# PCB_Reflow0xPIT.net
KiCad netlist of a schematic drawn in EAGLE
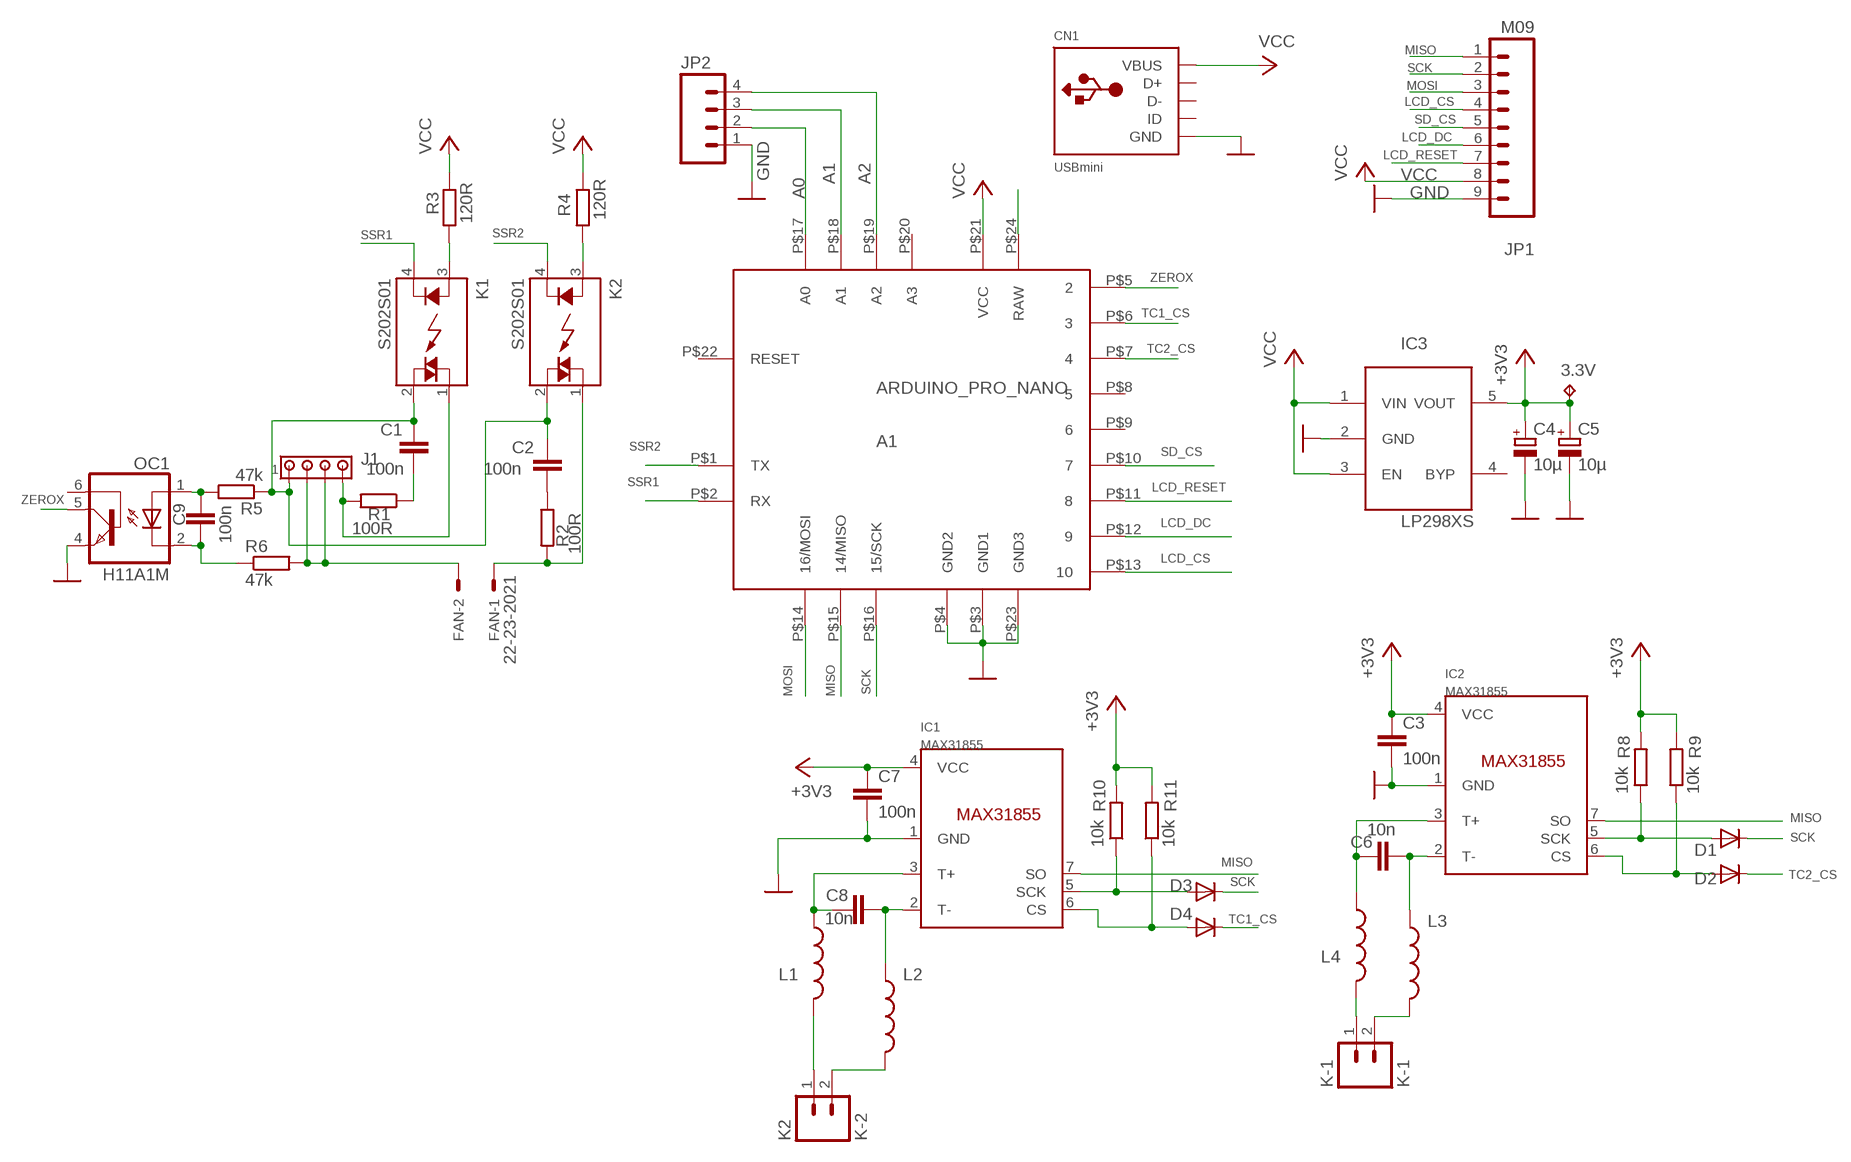
[diagram p0: schematic, sheet 1]

(export (version "E")
  (design (tool "Eeschema 10.0.6"))
  (components
    (comp (ref "3.3V")
      (value "TPTP08R")
      (footprint "eagle-import:TP08R")
      (libsource (lib "eagle-import") (part "TPTP08R"))
    )
    (comp (ref "A1")
      (value "ARDUINO_PRO_NANO")
      (footprint "eagle-import:ARDUINO_PRO_NANO")
      (libsource (lib "eagle-import") (part "ARDUINO_PRO_NANO"))
    )
    (comp (ref "C1")
      (value "100n")
      (footprint "eagle-import:C102-043X133")
      (libsource (lib "eagle-import") (part "C-EU102-043X133"))
    )
    (comp (ref "C2")
      (value "100n")
      (footprint "eagle-import:C102-043X133")
      (libsource (lib "eagle-import") (part "C-EU102-043X133"))
    )
    (comp (ref "C3")
      (value "100n")
      (footprint "eagle-import:C0805")
      (libsource (lib "eagle-import") (part "C-EUC0805"))
    )
    (comp (ref "C4")
      (value "10µ")
      (footprint "eagle-import:C_6032-28R")
      (libsource (lib "eagle-import") (part "CPOL-EUC/6032-28R"))
    )
    (comp (ref "C5")
      (value "10µ")
      (footprint "eagle-import:C_6032-28R")
      (libsource (lib "eagle-import") (part "CPOL-EUC/6032-28R"))
    )
    (comp (ref "C6")
      (value "10n")
      (footprint "eagle-import:C0603")
      (libsource (lib "eagle-import") (part "C-EUC0603"))
    )
    (comp (ref "C7")
      (value "100n")
      (footprint "eagle-import:C0805")
      (libsource (lib "eagle-import") (part "C-EUC0805"))
    )
    (comp (ref "C8")
      (value "10n")
      (footprint "eagle-import:C0603")
      (libsource (lib "eagle-import") (part "C-EUC0603"))
    )
    (comp (ref "C9")
      (value "100n")
      (footprint "eagle-import:C025-025X050")
      (libsource (lib "eagle-import") (part "C-EU025-025X050"))
    )
    (comp (ref "CN1")
      (value "USBmini")
      (footprint "eagle-import:USB-MINIB")
      (libsource (lib "eagle-import") (part "USBMINIB"))
    )
    (comp (ref "D1")
      (value "1N4148")
      (footprint "eagle-import:SOD-123")
      (libsource (lib "eagle-import") (part "DIODESOD-123"))
    )
    (comp (ref "D2")
      (value "1N4148")
      (footprint "eagle-import:SOD-123")
      (libsource (lib "eagle-import") (part "DIODESOD-123"))
    )
    (comp (ref "D3")
      (value "1N4148")
      (footprint "eagle-import:SOD-123")
      (libsource (lib "eagle-import") (part "DIODESOD-123"))
    )
    (comp (ref "D4")
      (value "1N4148")
      (footprint "eagle-import:SOD-123")
      (libsource (lib "eagle-import") (part "DIODESOD-123"))
    )
    (comp (ref "FAN")
      (value "22-23-2021")
      (footprint "eagle-import:22-23-2021")
      (fields (field (name "MF") "MOLEX"))
      (libsource (lib "eagle-import") (part "22-23-2021"))
    )
    (comp (ref "IC1")
      (value "MAX31855")
      (footprint "eagle-import:SOIC8")
      (libsource (lib "eagle-import") (part "MAX31855"))
    )
    (comp (ref "IC2")
      (value "MAX31855")
      (footprint "eagle-import:SOIC8")
      (libsource (lib "eagle-import") (part "MAX31855"))
    )
    (comp (ref "IC3")
      (value "LP298XS")
      (footprint "eagle-import:SOT23-5L")
      (libsource (lib "eagle-import") (part "LP298XS"))
    )
    (comp (ref "J1")
      (value "MTA04-156")
      (footprint "eagle-import:1X4MTA")
      (libsource (lib "eagle-import") (part "MTA04-156"))
    )
    (comp (ref "JP1")
      (value "M09")
      (footprint "eagle-import:1X09")
      (libsource (lib "eagle-import") (part "M09"))
    )
    (comp (ref "JP2")
      (value "M04LOCK")
      (footprint "eagle-import:1X04_LOCK")
      (libsource (lib "eagle-import") (part "M04LOCK"))
    )
    (comp (ref "K-1")
      (value "K-1")
      (footprint "eagle-import:JST-2-PTH")
      (libsource (lib "eagle-import") (part "M02JST-PTH-2"))
    )
    (comp (ref "K-2")
      (value "K2")
      (footprint "eagle-import:JST-2-PTH")
      (libsource (lib "eagle-import") (part "M02JST-PTH-2"))
    )
    (comp (ref "K1")
      (value "S202S01")
      (footprint "eagle-import:S102S01")
      (fields (field (name "MPN") "S202S01F"))
      (libsource (lib "eagle-import") (part "S?202S01"))
    )
    (comp (ref "K2")
      (value "S202S01")
      (footprint "eagle-import:S102S01")
      (fields (field (name "MPN") "S202S01F"))
      (libsource (lib "eagle-import") (part "S?202S01"))
    )
    (comp (ref "L1")
      (value "INDUCTOR0402")
      (footprint "eagle-import:C0402")
      (libsource (lib "eagle-import") (part "INDUCTOR0402"))
    )
    (comp (ref "L2")
      (value "INDUCTOR0402")
      (footprint "eagle-import:C0402")
      (libsource (lib "eagle-import") (part "INDUCTOR0402"))
    )
    (comp (ref "L3")
      (value "INDUCTOR0402")
      (footprint "eagle-import:C0402")
      (libsource (lib "eagle-import") (part "INDUCTOR0402"))
    )
    (comp (ref "L4")
      (value "INDUCTOR0402")
      (footprint "eagle-import:C0402")
      (libsource (lib "eagle-import") (part "INDUCTOR0402"))
    )
    (comp (ref "OC1")
      (value "H11A1M")
      (footprint "eagle-import:DIL06")
      (fields (field (name "MPN") "H11A1-M"))
      (libsource (lib "eagle-import") (part "H11A?M1"))
    )
    (comp (ref "R1")
      (value "100R")
      (footprint "eagle-import:0207_5V")
      (libsource (lib "eagle-import") (part "R-EU_0207/5V"))
    )
    (comp (ref "R2")
      (value "100R")
      (footprint "eagle-import:0207_5V")
      (libsource (lib "eagle-import") (part "R-EU_0207/5V"))
    )
    (comp (ref "R3")
      (value "120R")
      (footprint "eagle-import:M0805")
      (libsource (lib "eagle-import") (part "R-EU_M0805"))
    )
    (comp (ref "R4")
      (value "120R")
      (footprint "eagle-import:M0805")
      (libsource (lib "eagle-import") (part "R-EU_M0805"))
    )
    (comp (ref "R5")
      (value "47k")
      (footprint "eagle-import:0207_2V")
      (libsource (lib "eagle-import") (part "R-EU_0207/2V"))
    )
    (comp (ref "R6")
      (value "47k")
      (footprint "eagle-import:0207_2V")
      (libsource (lib "eagle-import") (part "R-EU_0207/2V"))
    )
    (comp (ref "R8")
      (value "10k")
      (footprint "eagle-import:M1206")
      (libsource (lib "eagle-import") (part "R-EU_M1206"))
    )
    (comp (ref "R9")
      (value "10k")
      (footprint "eagle-import:M1206")
      (libsource (lib "eagle-import") (part "R-EU_M1206"))
    )
    (comp (ref "R10")
      (value "10k")
      (footprint "eagle-import:M1206")
      (libsource (lib "eagle-import") (part "R-EU_M1206"))
    )
    (comp (ref "R11")
      (value "10k")
      (footprint "eagle-import:M1206")
      (libsource (lib "eagle-import") (part "R-EU_M1206"))
    )
  )
  (nets
    (net (code "1") (name "+3V3") (class "Default")
      (node (ref "3.3V") (pin "TP") (pinfunction "TP_TP") (pintype "input"))
      (node (ref "C3") (pin "1") (pinfunction "1_1") (pintype "passive"))
      (node (ref "C4") (pin "+") (pinfunction "+_+") (pintype "passive"))
      (node (ref "C5") (pin "+") (pinfunction "+_+") (pintype "passive"))
      (node (ref "C7") (pin "1") (pinfunction "1_1") (pintype "passive"))
      (node (ref "IC1") (pin "4") (pinfunction "VCC_4") (pintype "power_in"))
      (node (ref "IC2") (pin "4") (pinfunction "VCC_4") (pintype "power_in"))
      (node (ref "IC3") (pin "5") (pinfunction "VOUT_5") (pintype "bidirectional"))
      (node (ref "R10") (pin "2") (pinfunction "2_2") (pintype "passive"))
      (node (ref "R11") (pin "2") (pinfunction "2_2") (pintype "passive"))
      (node (ref "R8") (pin "2") (pinfunction "2_2") (pintype "passive"))
      (node (ref "R9") (pin "2") (pinfunction "2_2") (pintype "passive"))
    )
    (net (code "2") (name "/A0") (class "Default")
      (node (ref "A1") (pin "P$17") (pinfunction "A0_P$17") (pintype "bidirectional"))
      (node (ref "JP2") (pin "2") (pinfunction "2_2") (pintype "passive"))
    )
    (net (code "3") (name "/A1") (class "Default")
      (node (ref "A1") (pin "P$18") (pinfunction "A1_P$18") (pintype "bidirectional"))
      (node (ref "JP2") (pin "3") (pinfunction "3_3") (pintype "passive"))
    )
    (net (code "4") (name "/A2") (class "Default")
      (node (ref "A1") (pin "P$19") (pinfunction "A2_P$19") (pintype "bidirectional"))
      (node (ref "JP2") (pin "4") (pinfunction "4_4") (pintype "passive"))
    )
    (net (code "5") (name "/LCD_CS") (class "Default")
      (node (ref "A1") (pin "P$13") (pinfunction "10_P$13") (pintype "bidirectional"))
      (node (ref "JP1") (pin "4") (pinfunction "4_4") (pintype "passive"))
    )
    (net (code "6") (name "/LCD_DC") (class "Default")
      (node (ref "A1") (pin "P$12") (pinfunction "9_P$12") (pintype "bidirectional"))
      (node (ref "JP1") (pin "6") (pinfunction "6_6") (pintype "passive"))
    )
    (net (code "7") (name "/LCD_RESET") (class "Default")
      (node (ref "A1") (pin "P$11") (pinfunction "8_P$11") (pintype "bidirectional"))
      (node (ref "JP1") (pin "7") (pinfunction "7_7") (pintype "passive"))
    )
    (net (code "8") (name "/MISO") (class "Default")
      (node (ref "A1") (pin "P$15") (pinfunction "14/MISO_P$15") (pintype "bidirectional"))
      (node (ref "IC1") (pin "7") (pinfunction "SO_7") (pintype "output"))
      (node (ref "IC2") (pin "7") (pinfunction "SO_7") (pintype "output"))
      (node (ref "JP1") (pin "1") (pinfunction "1_1") (pintype "passive"))
    )
    (net (code "9") (name "/MOSI") (class "Default")
      (node (ref "A1") (pin "P$14") (pinfunction "16/MOSI_P$14") (pintype "bidirectional"))
      (node (ref "JP1") (pin "3") (pinfunction "3_3") (pintype "passive"))
    )
    (net (code "10") (name "/SCK") (class "Default")
      (node (ref "A1") (pin "P$16") (pinfunction "15/SCK_P$16") (pintype "bidirectional"))
      (node (ref "D1") (pin "C") (pinfunction "C_C") (pintype "passive"))
      (node (ref "D3") (pin "C") (pinfunction "C_C") (pintype "passive"))
      (node (ref "JP1") (pin "2") (pinfunction "2_2") (pintype "passive"))
    )
    (net (code "11") (name "/SD_CS") (class "Default")
      (node (ref "A1") (pin "P$10") (pinfunction "7_P$10") (pintype "bidirectional"))
      (node (ref "JP1") (pin "5") (pinfunction "5_5") (pintype "passive"))
    )
    (net (code "12") (name "/SSR1") (class "Default")
      (node (ref "A1") (pin "P$2") (pinfunction "RX_P$2") (pintype "bidirectional"))
      (node (ref "K1") (pin "4") (pinfunction "K_4") (pintype "passive"))
    )
    (net (code "13") (name "/SSR2") (class "Default")
      (node (ref "A1") (pin "P$1") (pinfunction "TX_P$1") (pintype "bidirectional"))
      (node (ref "K2") (pin "4") (pinfunction "K_4") (pintype "passive"))
    )
    (net (code "14") (name "/TC1_CS") (class "Default")
      (node (ref "A1") (pin "P$6") (pinfunction "3_P$6") (pintype "bidirectional"))
      (node (ref "D4") (pin "C") (pinfunction "C_C") (pintype "passive"))
    )
    (net (code "15") (name "/TC2_CS") (class "Default")
      (node (ref "A1") (pin "P$7") (pinfunction "4_P$7") (pintype "bidirectional"))
      (node (ref "D2") (pin "C") (pinfunction "C_C") (pintype "passive"))
    )
    (net (code "16") (name "/ZEROX") (class "Default")
      (node (ref "A1") (pin "P$5") (pinfunction "2_P$5") (pintype "bidirectional"))
      (node (ref "OC1") (pin "5") (pinfunction "COL_5") (pintype "passive"))
    )
    (net (code "17") (name "GND") (class "Default")
      (node (ref "A1") (pin "P$23") (pinfunction "GND3_P$23") (pintype "power_in"))
      (node (ref "A1") (pin "P$3") (pinfunction "GND1_P$3") (pintype "power_in"))
      (node (ref "A1") (pin "P$4") (pinfunction "GND2_P$4") (pintype "power_in"))
      (node (ref "C3") (pin "2") (pinfunction "2_2") (pintype "passive"))
      (node (ref "C4") (pin "-") (pinfunction "-_-") (pintype "passive"))
      (node (ref "C5") (pin "-") (pinfunction "-_-") (pintype "passive"))
      (node (ref "C7") (pin "2") (pinfunction "2_2") (pintype "passive"))
      (node (ref "CN1") (pin "GND") (pinfunction "GND_GND") (pintype "power_in"))
      (node (ref "IC1") (pin "1") (pinfunction "GND_1") (pintype "power_in"))
      (node (ref "IC2") (pin "1") (pinfunction "GND_1") (pintype "power_in"))
      (node (ref "IC3") (pin "2") (pinfunction "GND_2") (pintype "bidirectional"))
      (node (ref "JP1") (pin "9") (pinfunction "9_9") (pintype "passive"))
      (node (ref "JP2") (pin "1") (pinfunction "1_1") (pintype "passive"))
      (node (ref "OC1") (pin "4") (pinfunction "EMI_4") (pintype "passive"))
    )
    (net (code "18") (name "Net-(C1-Pad2)") (class "Default")
      (node (ref "C1") (pin "2") (pinfunction "2_2") (pintype "passive"))
      (node (ref "R1") (pin "1") (pinfunction "1_1") (pintype "passive"))
    )
    (net (code "19") (name "Net-(C2-Pad2)") (class "Default")
      (node (ref "C2") (pin "2") (pinfunction "2_2") (pintype "passive"))
      (node (ref "R2") (pin "1") (pinfunction "1_1") (pintype "passive"))
    )
    (net (code "20") (name "Net-(FANA-S)") (class "Default")
      (node (ref "FAN") (pin "1") (pinfunction "S_1") (pintype "passive"))
      (node (ref "K2") (pin "1") (pinfunction "DS1_1") (pintype "passive"))
      (node (ref "R2") (pin "2") (pinfunction "2_2") (pintype "passive"))
    )
    (net (code "21") (name "Net-(FANB-S)") (class "Default")
      (node (ref "FAN") (pin "2") (pinfunction "S_2") (pintype "passive"))
      (node (ref "J1") (pin "2") (pinfunction "2_2") (pintype "passive"))
      (node (ref "J1") (pin "3") (pinfunction "3_3") (pintype "passive"))
      (node (ref "R6") (pin "2") (pinfunction "2_2") (pintype "passive"))
    )
    (net (code "22") (name "Net-(IC1-CS)") (class "Default")
      (node (ref "D4") (pin "A") (pinfunction "A_A") (pintype "passive"))
      (node (ref "IC1") (pin "6") (pinfunction "CS_6") (pintype "input"))
      (node (ref "R11") (pin "1") (pinfunction "1_1") (pintype "passive"))
    )
    (net (code "23") (name "Net-(IC1-SCK)") (class "Default")
      (node (ref "D3") (pin "A") (pinfunction "A_A") (pintype "passive"))
      (node (ref "IC1") (pin "5") (pinfunction "SCK_5") (pintype "input"))
      (node (ref "R10") (pin "1") (pinfunction "1_1") (pintype "passive"))
    )
    (net (code "24") (name "Net-(IC1-T+)") (class "Default")
      (node (ref "C8") (pin "1") (pinfunction "1_1") (pintype "passive"))
      (node (ref "IC1") (pin "3") (pinfunction "T+_3") (pintype "input"))
      (node (ref "L1") (pin "1") (pinfunction "1_1") (pintype "passive"))
    )
    (net (code "25") (name "Net-(IC1-T-)") (class "Default")
      (node (ref "C8") (pin "2") (pinfunction "2_2") (pintype "passive"))
      (node (ref "IC1") (pin "2") (pinfunction "T-_2") (pintype "input"))
      (node (ref "L2") (pin "1") (pinfunction "1_1") (pintype "passive"))
    )
    (net (code "26") (name "Net-(IC2-CS)") (class "Default")
      (node (ref "D2") (pin "A") (pinfunction "A_A") (pintype "passive"))
      (node (ref "IC2") (pin "6") (pinfunction "CS_6") (pintype "input"))
      (node (ref "R9") (pin "1") (pinfunction "1_1") (pintype "passive"))
    )
    (net (code "27") (name "Net-(IC2-SCK)") (class "Default")
      (node (ref "D1") (pin "A") (pinfunction "A_A") (pintype "passive"))
      (node (ref "IC2") (pin "5") (pinfunction "SCK_5") (pintype "input"))
      (node (ref "R8") (pin "1") (pinfunction "1_1") (pintype "passive"))
    )
    (net (code "28") (name "Net-(IC2-T+)") (class "Default")
      (node (ref "C6") (pin "1") (pinfunction "1_1") (pintype "passive"))
      (node (ref "IC2") (pin "3") (pinfunction "T+_3") (pintype "input"))
      (node (ref "L4") (pin "1") (pinfunction "1_1") (pintype "passive"))
    )
    (net (code "29") (name "Net-(IC2-T-)") (class "Default")
      (node (ref "C6") (pin "2") (pinfunction "2_2") (pintype "passive"))
      (node (ref "IC2") (pin "2") (pinfunction "T-_2") (pintype "input"))
      (node (ref "L3") (pin "1") (pinfunction "1_1") (pintype "passive"))
    )
    (net (code "30") (name "Net-(K-1-Pad1)") (class "Default")
      (node (ref "K-1") (pin "1") (pinfunction "1_1") (pintype "passive"))
      (node (ref "L4") (pin "2") (pinfunction "2_2") (pintype "passive"))
    )
    (net (code "31") (name "Net-(K-1-Pad2)") (class "Default")
      (node (ref "K-1") (pin "2") (pinfunction "2_2") (pintype "passive"))
      (node (ref "L3") (pin "2") (pinfunction "2_2") (pintype "passive"))
    )
    (net (code "32") (name "Net-(K-2-Pad1)") (class "Default")
      (node (ref "K-2") (pin "1") (pinfunction "1_1") (pintype "passive"))
      (node (ref "L1") (pin "2") (pinfunction "2_2") (pintype "passive"))
    )
    (net (code "33") (name "Net-(K-2-Pad2)") (class "Default")
      (node (ref "K-2") (pin "2") (pinfunction "2_2") (pintype "passive"))
      (node (ref "L2") (pin "2") (pinfunction "2_2") (pintype "passive"))
    )
    (net (code "34") (name "Net-(K1-A)") (class "Default")
      (node (ref "K1") (pin "3") (pinfunction "A_3") (pintype "passive"))
      (node (ref "R3") (pin "2") (pinfunction "2_2") (pintype "passive"))
    )
    (net (code "35") (name "Net-(K1-DS1)") (class "Default")
      (node (ref "J1") (pin "4") (pinfunction "4_4") (pintype "passive"))
      (node (ref "K1") (pin "1") (pinfunction "DS1_1") (pintype "passive"))
      (node (ref "R1") (pin "2") (pinfunction "2_2") (pintype "passive"))
    )
    (net (code "36") (name "Net-(K1-DS2)") (class "Default")
      (node (ref "C1") (pin "1") (pinfunction "1_1") (pintype "passive"))
      (node (ref "C2") (pin "1") (pinfunction "1_1") (pintype "passive"))
      (node (ref "J1") (pin "1") (pinfunction "1_1") (pintype "passive"))
      (node (ref "K1") (pin "2") (pinfunction "DS2_2") (pintype "passive"))
      (node (ref "K2") (pin "2") (pinfunction "DS2_2") (pintype "passive"))
      (node (ref "R5") (pin "1") (pinfunction "1_1") (pintype "passive"))
    )
    (net (code "37") (name "Net-(K2-A)") (class "Default")
      (node (ref "K2") (pin "3") (pinfunction "A_3") (pintype "passive"))
      (node (ref "R4") (pin "2") (pinfunction "2_2") (pintype "passive"))
    )
    (net (code "38") (name "Net-(OC1-A)") (class "Default")
      (node (ref "C9") (pin "1") (pinfunction "1_1") (pintype "passive"))
      (node (ref "OC1") (pin "1") (pinfunction "A_1") (pintype "passive"))
      (node (ref "R5") (pin "2") (pinfunction "2_2") (pintype "passive"))
    )
    (net (code "39") (name "Net-(OC1-C)") (class "Default")
      (node (ref "C9") (pin "2") (pinfunction "2_2") (pintype "passive"))
      (node (ref "OC1") (pin "2") (pinfunction "C_2") (pintype "passive"))
      (node (ref "R6") (pin "1") (pinfunction "1_1") (pintype "passive"))
    )
    (net (code "40") (name "VCC") (class "Default")
      (node (ref "A1") (pin "P$21") (pinfunction "VCC_P$21") (pintype "power_in"))
      (node (ref "CN1") (pin "VBUS") (pinfunction "VBUS_VBUS") (pintype "power_in"))
      (node (ref "IC3") (pin "1") (pinfunction "VIN_1") (pintype "bidirectional"))
      (node (ref "IC3") (pin "3") (pinfunction "EN_3") (pintype "bidirectional"))
      (node (ref "JP1") (pin "8") (pinfunction "8_8") (pintype "passive"))
      (node (ref "R3") (pin "1") (pinfunction "1_1") (pintype "passive"))
      (node (ref "R4") (pin "1") (pinfunction "1_1") (pintype "passive"))
    )
    (net (code "41") (name "unconnected-(A1-5-PadP$8)") (class "Default")
      (node (ref "A1") (pin "P$8") (pinfunction "5_P$8") (pintype "bidirectional"))
    )
    (net (code "42") (name "unconnected-(A1-6-PadP$9)") (class "Default")
      (node (ref "A1") (pin "P$9") (pinfunction "6_P$9") (pintype "bidirectional"))
    )
    (net (code "43") (name "unconnected-(A1-A3-PadP$20)") (class "Default")
      (node (ref "A1") (pin "P$20") (pinfunction "A3_P$20") (pintype "bidirectional"))
    )
    (net (code "44") (name "unconnected-(A1-RAW-PadP$24)") (class "Default")
      (node (ref "A1") (pin "P$24") (pinfunction "RAW_P$24") (pintype "power_in"))
    )
    (net (code "45") (name "unconnected-(A1-RESET-PadP$22)") (class "Default")
      (node (ref "A1") (pin "P$22") (pinfunction "RESET_P$22") (pintype "bidirectional"))
    )
    (net (code "46") (name "unconnected-(CN1-PadD+)") (class "Default")
      (node (ref "CN1") (pin "D+") (pinfunction "D+_D+") (pintype "bidirectional"))
    )
    (net (code "47") (name "unconnected-(CN1-PadD-)") (class "Default")
      (node (ref "CN1") (pin "D-") (pinfunction "D-_D-") (pintype "bidirectional"))
    )
    (net (code "48") (name "unconnected-(CN1-PadID)") (class "Default")
      (node (ref "CN1") (pin "ID") (pinfunction "ID_ID") (pintype "bidirectional"))
    )
    (net (code "49") (name "unconnected-(IC3-BYP-Pad4)") (class "Default")
      (node (ref "IC3") (pin "4") (pinfunction "BYP_4") (pintype "bidirectional"))
    )
    (net (code "50") (name "unconnected-(OC1-BAS-Pad6)") (class "Default")
      (node (ref "OC1") (pin "6") (pinfunction "BAS_6") (pintype "passive"))
    )
  )
)
